# 01-Amplifier.net
KiCad netlist of a schematic drawn in Altium Designer
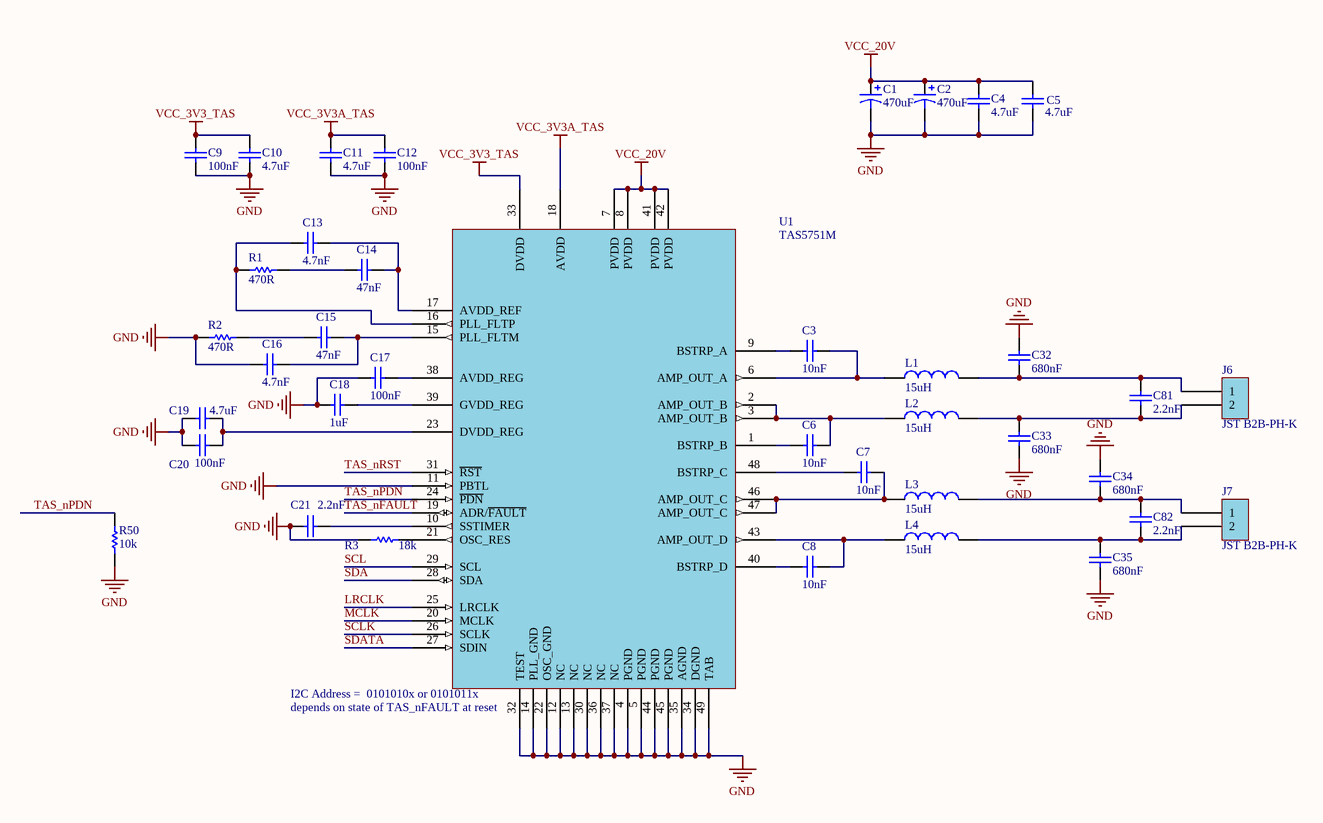
[diagram p0: 01-Amplifier.SchDoc]

(export (version "E")
  (design (tool "Eeschema 10.0.6"))
  (components
    (comp (ref "C1")
      (value "470uF")
      (footprint "Aptustech:Cap_POL_10mm_12.5mm_TH")
      (description "Aluminum Capacitor 470uF 25V TH 10mm 12.5mm")
      (fields (field (name "VOLTAGE") "25V") (field (name "TOLERANCE") "20%"))
      (libsource (lib "Cap_Aluminum") (part "470uF 25V 10mm 12.5mm"))
    )
    (comp (ref "C2")
      (value "470uF")
      (footprint "Aptustech:Cap_POL_10mm_12.5mm_TH")
      (description "Aluminum Capacitor 470uF 25V TH 10mm 12.5mm")
      (fields (field (name "VOLTAGE") "25V") (field (name "TOLERANCE") "20%"))
      (libsource (lib "Cap_Aluminum") (part "470uF 25V 10mm 12.5mm"))
    )
    (comp (ref "C3")
      (value "10nF")
      (footprint "Aptustech:CAPC3216X16N")
      (description "10nF 50V 1206 X7R")
      (fields (field (name "VOLTAGE") "50V") (field (name "TOLERANCE") "10%"))
      (libsource (lib "Cap_1206") (part "10nF 50V 1206 X7R"))
    )
    (comp (ref "C4")
      (value "4.7uF")
      (footprint "Aptustech:CAPC3216X16N")
      (description "4.7uF 50V 1206 X5R")
      (fields (field (name "VOLTAGE") "50V") (field (name "TOLERANCE") "10%"))
      (libsource (lib "Cap_1206") (part "4.7uF 50V 1206 X5R"))
    )
    (comp (ref "C5")
      (value "4.7uF")
      (footprint "Aptustech:CAPC3216X16N")
      (description "4.7uF 50V 1206 X5R")
      (fields (field (name "VOLTAGE") "50V") (field (name "TOLERANCE") "10%"))
      (libsource (lib "Cap_1206") (part "4.7uF 50V 1206 X5R"))
    )
    (comp (ref "C6")
      (value "10nF")
      (footprint "Aptustech:CAPC3216X16N")
      (description "10nF 50V 1206 X7R")
      (fields (field (name "VOLTAGE") "50V") (field (name "TOLERANCE") "10%"))
      (libsource (lib "Cap_1206") (part "10nF 50V 1206 X7R"))
    )
    (comp (ref "C7")
      (value "10nF")
      (footprint "Aptustech:CAPC3216X16N")
      (description "10nF 50V 1206 X7R")
      (fields (field (name "VOLTAGE") "50V") (field (name "TOLERANCE") "10%"))
      (libsource (lib "Cap_1206") (part "10nF 50V 1206 X7R"))
    )
    (comp (ref "C8")
      (value "10nF")
      (footprint "Aptustech:CAPC3216X16N")
      (description "10nF 50V 1206 X7R")
      (fields (field (name "VOLTAGE") "50V") (field (name "TOLERANCE") "10%"))
      (libsource (lib "Cap_1206") (part "10nF 50V 1206 X7R"))
    )
    (comp (ref "C9")
      (value "100nF")
      (footprint "Aptustech:CAPC1608X06N")
      (description "100nF 25V 0603 X5R")
      (fields (field (name "VOLTAGE") "25V") (field (name "TOLERANCE") "10%"))
      (libsource (lib "Cap_0603") (part "100nF 25V 0603 X5R"))
    )
    (comp (ref "C10")
      (value "4.7uF")
      (footprint "Aptustech:CAPC1608X06N")
      (description "4.7uF 10V 0603 X5R")
      (fields (field (name "VOLTAGE") "10V") (field (name "TOLERANCE") "10%"))
      (libsource (lib "Cap_0603") (part "4.7uF 10V 0603 X5R"))
    )
    (comp (ref "C11")
      (value "4.7uF")
      (footprint "Aptustech:CAPC1608X06N")
      (description "4.7uF 10V 0603 X5R")
      (fields (field (name "VOLTAGE") "10V") (field (name "TOLERANCE") "10%"))
      (libsource (lib "Cap_0603") (part "4.7uF 10V 0603 X5R"))
    )
    (comp (ref "C12")
      (value "100nF")
      (footprint "Aptustech:CAPC1608X06N")
      (description "100nF 25V 0603 X5R")
      (fields (field (name "VOLTAGE") "25V") (field (name "TOLERANCE") "10%"))
      (libsource (lib "Cap_0603") (part "100nF 25V 0603 X5R"))
    )
    (comp (ref "C13")
      (value "4.7nF")
      (footprint "Aptustech:CAPC1608X06N")
      (description "4.7nF 50V 0603 X7R")
      (fields (field (name "VOLTAGE") "50V") (field (name "TOLERANCE") "10%"))
      (libsource (lib "Cap_0603") (part "4.7nF 50V 0603 X7R"))
    )
    (comp (ref "C14")
      (value "47nF")
      (footprint "Aptustech:CAPC1608X06N")
      (description "47nF 50V 0603 X7R")
      (fields (field (name "VOLTAGE") "50V") (field (name "TOLERANCE") "10%"))
      (libsource (lib "Cap_0603") (part "47nF 50V 0603 X7R"))
    )
    (comp (ref "C15")
      (value "47nF")
      (footprint "Aptustech:CAPC1608X06N")
      (description "47nF 50V 0603 X7R")
      (fields (field (name "VOLTAGE") "50V") (field (name "TOLERANCE") "10%"))
      (libsource (lib "Cap_0603") (part "47nF 50V 0603 X7R"))
    )
    (comp (ref "C16")
      (value "4.7nF")
      (footprint "Aptustech:CAPC1608X06N")
      (description "4.7nF 50V 0603 X7R")
      (fields (field (name "VOLTAGE") "50V") (field (name "TOLERANCE") "10%"))
      (libsource (lib "Cap_0603") (part "4.7nF 50V 0603 X7R"))
    )
    (comp (ref "C17")
      (value "100nF")
      (footprint "Aptustech:CAPC1608X06N")
      (description "100nF 25V 0603 X5R")
      (fields (field (name "VOLTAGE") "25V") (field (name "TOLERANCE") "10%"))
      (libsource (lib "Cap_0603") (part "100nF 25V 0603 X5R"))
    )
    (comp (ref "C18")
      (value "1uF")
      (footprint "Aptustech:CAPC1608X06N")
      (description "1uF 16V 0603 X7R")
      (fields (field (name "VOLTAGE") "16V") (field (name "TOLERANCE") "10%"))
      (libsource (lib "Cap_0603") (part "1uF 16V 0603 X7R"))
    )
    (comp (ref "C19")
      (value "4.7uF")
      (footprint "Aptustech:CAPC1608X06N")
      (description "4.7uF 10V 0603 X5R")
      (fields (field (name "VOLTAGE") "10V") (field (name "TOLERANCE") "10%"))
      (libsource (lib "Cap_0603") (part "4.7uF 10V 0603 X5R"))
    )
    (comp (ref "C20")
      (value "100nF")
      (footprint "Aptustech:CAPC1608X06N")
      (description "100nF 25V 0603 X5R")
      (fields (field (name "VOLTAGE") "25V") (field (name "TOLERANCE") "10%"))
      (libsource (lib "Cap_0603") (part "100nF 25V 0603 X5R"))
    )
    (comp (ref "C21")
      (value "2.2nF")
      (footprint "Aptustech:CAPC1608X06N")
      (description "2.2nF 50V 0603 X7R")
      (fields (field (name "VOLTAGE") "50V") (field (name "TOLERANCE") "10%"))
      (libsource (lib "Cap_0603") (part "2.2nF 50V 0603 X7R"))
    )
    (comp (ref "C32")
      (value "680nF")
      (footprint "Aptustech:CAPC3216X16N")
      (description "680nF 50V 1206 C0G")
      (fields (field (name "VOLTAGE") "50V") (field (name "TOLERANCE") "10%"))
      (libsource (lib "Cap_1206") (part "680nF 50V 1206 C0G"))
    )
    (comp (ref "C33")
      (value "680nF")
      (footprint "Aptustech:CAPC3216X16N")
      (description "680nF 50V 1206 C0G")
      (fields (field (name "VOLTAGE") "50V") (field (name "TOLERANCE") "10%"))
      (libsource (lib "Cap_1206") (part "680nF 50V 1206 C0G"))
    )
    (comp (ref "C34")
      (value "680nF")
      (footprint "Aptustech:CAPC3216X16N")
      (description "680nF 50V 1206 C0G")
      (fields (field (name "VOLTAGE") "50V") (field (name "TOLERANCE") "10%"))
      (libsource (lib "Cap_1206") (part "680nF 50V 1206 C0G"))
    )
    (comp (ref "C35")
      (value "680nF")
      (footprint "Aptustech:CAPC3216X16N")
      (description "680nF 50V 1206 C0G")
      (fields (field (name "VOLTAGE") "50V") (field (name "TOLERANCE") "10%"))
      (libsource (lib "Cap_1206") (part "680nF 50V 1206 C0G"))
    )
    (comp (ref "C81")
      (value "2.2nF")
      (footprint "Aptustech:CAPC1608X06N")
      (description "2.2nF 50V 0603 X7R")
      (fields (field (name "VOLTAGE") "50V") (field (name "TOLERANCE") "10%"))
      (libsource (lib "Cap_0603") (part "2.2nF 50V 0603 X7R"))
    )
    (comp (ref "C82")
      (value "2.2nF")
      (footprint "Aptustech:CAPC1608X06N")
      (description "2.2nF 50V 0603 X7R")
      (fields (field (name "VOLTAGE") "50V") (field (name "TOLERANCE") "10%"))
      (libsource (lib "Cap_0603") (part "2.2nF 50V 0603 X7R"))
    )
    (comp (ref "J6")
      (value "JST B2B-PH-K")
      (footprint "Aptustech:JST B2B-PH-K")
      (fields (field (name "PARTNUMBER") "B2B-PH-K") (field (name "MANUFACTURER") "JST"))
      (libsource (lib "Connectors") (part "JST B2B-PH-K"))
    )
    (comp (ref "J7")
      (value "JST B2B-PH-K")
      (footprint "Aptustech:JST B2B-PH-K")
      (fields (field (name "PARTNUMBER") "B2B-PH-K") (field (name "MANUFACTURER") "JST"))
      (libsource (lib "Connectors") (part "JST B2B-PH-K"))
    )
    (comp (ref "L1")
      (value "15uH")
      (footprint "Aptustech:1255AY")
      (description "1255AY-150M")
      (fields (field (name "MANUFACTURER") "Murata"))
      (libsource (lib "Inductor") (part "1255AY-150M"))
    )
    (comp (ref "L2")
      (value "15uH")
      (footprint "Aptustech:1255AY")
      (description "1255AY-150M")
      (fields (field (name "MANUFACTURER") "Murata"))
      (libsource (lib "Inductor") (part "1255AY-150M"))
    )
    (comp (ref "L3")
      (value "15uH")
      (footprint "Aptustech:1255AY")
      (description "1255AY-150M")
      (fields (field (name "MANUFACTURER") "Murata"))
      (libsource (lib "Inductor") (part "1255AY-150M"))
    )
    (comp (ref "L4")
      (value "15uH")
      (footprint "Aptustech:1255AY")
      (description "1255AY-150M")
      (fields (field (name "MANUFACTURER") "Murata"))
      (libsource (lib "Inductor") (part "1255AY-150M"))
    )
    (comp (ref "R1")
      (value "470R")
      (footprint "Aptustech:RESC1608X06N")
      (description "Resistor 470R 0603 1%")
      (fields (field (name "TOLERANCE") "1%") (field (name "Comment") "470R_0603"))
      (libsource (lib "Res_0603") (part "470R"))
    )
    (comp (ref "R2")
      (value "470R")
      (footprint "Aptustech:RESC1608X06N")
      (description "Resistor 470R 0603 1%")
      (fields (field (name "TOLERANCE") "1%") (field (name "Comment") "470R_0603"))
      (libsource (lib "Res_0603") (part "470R"))
    )
    (comp (ref "R3")
      (value "18k")
      (footprint "Aptustech:RESC1608X06N")
      (description "Resistor 18k 0603 1%")
      (fields (field (name "TOLERANCE") "1%") (field (name "Comment") "18k_0603"))
      (libsource (lib "Res_0603") (part "18k"))
    )
    (comp (ref "R50")
      (value "10k")
      (footprint "Aptustech:RESC1608X06N")
      (description "Resistor 10k 0603 1%")
      (fields (field (name "TOLERANCE") "1%") (field (name "Comment") "10k_0603"))
      (libsource (lib "Res_0603") (part "10k"))
    )
    (comp (ref "U1")
      (value "TAS5751M")
      (footprint "Aptustech:TSSOP50P810X120_HS-49M")
      (description "TAS5751M - Digital Input Audio Power Amplifier with EQ and 3-Band AGL")
      (fields (field (name "MANUFACTURER") "TI"))
      (libsource (lib "Audio") (part "TAS5751M"))
    )
  )
  (nets
    (net (code "1") (name "/LRCLK") (class "Default")
      (node (ref "U1") (pin "25") (pinfunction "LRCLK_25") (pintype "input"))
    )
    (net (code "2") (name "/MCLK") (class "Default")
      (node (ref "U1") (pin "20") (pinfunction "MCLK_20") (pintype "input"))
    )
    (net (code "3") (name "/SCL") (class "Default")
      (node (ref "U1") (pin "29") (pinfunction "SCL_29") (pintype "input"))
    )
    (net (code "4") (name "/SCLK") (class "Default")
      (node (ref "U1") (pin "26") (pinfunction "SCLK_26") (pintype "input"))
    )
    (net (code "5") (name "/SDA") (class "Default")
      (node (ref "U1") (pin "28") (pinfunction "SDA_28") (pintype "bidirectional"))
    )
    (net (code "6") (name "/SDATA") (class "Default")
      (node (ref "U1") (pin "27") (pinfunction "SDIN_27") (pintype "input"))
    )
    (net (code "7") (name "/TAS_nFAULT") (class "Default")
      (node (ref "U1") (pin "19") (pinfunction "ADR/~{FAULT}_19") (pintype "bidirectional"))
    )
    (net (code "8") (name "/TAS_nPDN") (class "Default")
      (node (ref "R50") (pin "1") (pinfunction "1_1") (pintype "passive"))
      (node (ref "U1") (pin "24") (pinfunction "~{PDN}_24") (pintype "input"))
    )
    (net (code "9") (name "/TAS_nRST") (class "Default")
      (node (ref "U1") (pin "31") (pinfunction "~{RST}_31") (pintype "input"))
    )
    (net (code "10") (name "GND") (class "Default")
      (node (ref "C1") (pin "2") (pinfunction "2_2") (pintype "passive"))
      (node (ref "C10") (pin "1") (pinfunction "1_1") (pintype "passive"))
      (node (ref "C11") (pin "1") (pinfunction "1_1") (pintype "passive"))
      (node (ref "C12") (pin "1") (pinfunction "1_1") (pintype "passive"))
      (node (ref "C16") (pin "1") (pinfunction "1_1") (pintype "passive"))
      (node (ref "C17") (pin "2") (pinfunction "2_2") (pintype "passive"))
      (node (ref "C18") (pin "1") (pinfunction "1_1") (pintype "passive"))
      (node (ref "C19") (pin "2") (pinfunction "2_2") (pintype "passive"))
      (node (ref "C2") (pin "2") (pinfunction "2_2") (pintype "passive"))
      (node (ref "C20") (pin "2") (pinfunction "2_2") (pintype "passive"))
      (node (ref "C21") (pin "1") (pinfunction "1_1") (pintype "passive"))
      (node (ref "C32") (pin "1") (pinfunction "1_1") (pintype "passive"))
      (node (ref "C33") (pin "1") (pinfunction "1_1") (pintype "passive"))
      (node (ref "C34") (pin "1") (pinfunction "1_1") (pintype "passive"))
      (node (ref "C35") (pin "1") (pinfunction "1_1") (pintype "passive"))
      (node (ref "C4") (pin "1") (pinfunction "1_1") (pintype "passive"))
      (node (ref "C5") (pin "1") (pinfunction "1_1") (pintype "passive"))
      (node (ref "C9") (pin "1") (pinfunction "1_1") (pintype "passive"))
      (node (ref "R2") (pin "1") (pinfunction "1_1") (pintype "passive"))
      (node (ref "R3") (pin "1") (pinfunction "1_1") (pintype "passive"))
      (node (ref "R50") (pin "2") (pinfunction "2_2") (pintype "passive"))
      (node (ref "U1") (pin "11") (pinfunction "PBTL_11") (pintype "input"))
      (node (ref "U1") (pin "12") (pinfunction "NC_12") (pintype "passive"))
      (node (ref "U1") (pin "13") (pinfunction "NC_13") (pintype "passive"))
      (node (ref "U1") (pin "14") (pinfunction "PLL_GND_14") (pintype "power_in"))
      (node (ref "U1") (pin "22") (pinfunction "OSC_GND_22") (pintype "power_in"))
      (node (ref "U1") (pin "30") (pinfunction "NC_30") (pintype "passive"))
      (node (ref "U1") (pin "32") (pinfunction "TEST_32") (pintype "passive"))
      (node (ref "U1") (pin "34") (pinfunction "DGND_34") (pintype "power_in"))
      (node (ref "U1") (pin "35") (pinfunction "AGND_35") (pintype "power_in"))
      (node (ref "U1") (pin "36") (pinfunction "NC_36") (pintype "passive"))
      (node (ref "U1") (pin "37") (pinfunction "NC_37") (pintype "passive"))
      (node (ref "U1") (pin "4") (pinfunction "PGND_4") (pintype "power_in"))
      (node (ref "U1") (pin "44") (pinfunction "PGND_44") (pintype "power_in"))
      (node (ref "U1") (pin "45") (pinfunction "PGND_45") (pintype "power_in"))
      (node (ref "U1") (pin "49") (pinfunction "TAB_49") (pintype "power_in"))
      (node (ref "U1") (pin "5") (pinfunction "PGND_5") (pintype "power_in"))
    )
    (net (code "11") (name "Net-(C6-Pad2)") (class "Default")
      (node (ref "C6") (pin "2") (pinfunction "2_2") (pintype "passive"))
      (node (ref "L2") (pin "1") (pinfunction "1_1") (pintype "passive"))
      (node (ref "U1") (pin "2") (pinfunction "AMP_OUT_B_2") (pintype "output"))
      (node (ref "U1") (pin "3") (pinfunction "AMP_OUT_B_3") (pintype "output"))
    )
    (net (code "12") (name "Net-(C7-Pad2)") (class "Default")
      (node (ref "C7") (pin "2") (pinfunction "2_2") (pintype "passive"))
      (node (ref "L3") (pin "1") (pinfunction "1_1") (pintype "passive"))
      (node (ref "U1") (pin "46") (pinfunction "AMP_OUT_C_46") (pintype "output"))
      (node (ref "U1") (pin "47") (pinfunction "AMP_OUT_C_47") (pintype "output"))
    )
    (net (code "13") (name "Net-(C14-Pad1)") (class "Default")
      (node (ref "C14") (pin "1") (pinfunction "1_1") (pintype "passive"))
      (node (ref "R1") (pin "2") (pinfunction "2_2") (pintype "passive"))
    )
    (net (code "14") (name "Net-(C15-Pad1)") (class "Default")
      (node (ref "C15") (pin "1") (pinfunction "1_1") (pintype "passive"))
      (node (ref "R2") (pin "2") (pinfunction "2_2") (pintype "passive"))
    )
    (net (code "15") (name "Net-(C32-Pad2)") (class "Default")
      (node (ref "C32") (pin "2") (pinfunction "2_2") (pintype "passive"))
      (node (ref "C81") (pin "2") (pinfunction "2_2") (pintype "passive"))
      (node (ref "J6") (pin "1") (pinfunction "1_1") (pintype "passive"))
      (node (ref "L1") (pin "2") (pinfunction "2_2") (pintype "passive"))
    )
    (net (code "16") (name "Net-(C33-Pad2)") (class "Default")
      (node (ref "C33") (pin "2") (pinfunction "2_2") (pintype "passive"))
      (node (ref "C81") (pin "1") (pinfunction "1_1") (pintype "passive"))
      (node (ref "J6") (pin "2") (pinfunction "2_2") (pintype "passive"))
      (node (ref "L2") (pin "2") (pinfunction "2_2") (pintype "passive"))
    )
    (net (code "17") (name "Net-(C34-Pad2)") (class "Default")
      (node (ref "C34") (pin "2") (pinfunction "2_2") (pintype "passive"))
      (node (ref "C82") (pin "2") (pinfunction "2_2") (pintype "passive"))
      (node (ref "J7") (pin "1") (pinfunction "1_1") (pintype "passive"))
      (node (ref "L3") (pin "2") (pinfunction "2_2") (pintype "passive"))
    )
    (net (code "18") (name "Net-(C35-Pad2)") (class "Default")
      (node (ref "C35") (pin "2") (pinfunction "2_2") (pintype "passive"))
      (node (ref "C82") (pin "1") (pinfunction "1_1") (pintype "passive"))
      (node (ref "J7") (pin "2") (pinfunction "2_2") (pintype "passive"))
      (node (ref "L4") (pin "2") (pinfunction "2_2") (pintype "passive"))
    )
    (net (code "19") (name "Net-(U1-AMP_OUT_A)") (class "Default")
      (node (ref "C3") (pin "2") (pinfunction "2_2") (pintype "passive"))
      (node (ref "L1") (pin "1") (pinfunction "1_1") (pintype "passive"))
      (node (ref "U1") (pin "6") (pinfunction "AMP_OUT_A_6") (pintype "output"))
    )
    (net (code "20") (name "Net-(U1-AMP_OUT_D)") (class "Default")
      (node (ref "C8") (pin "2") (pinfunction "2_2") (pintype "passive"))
      (node (ref "L4") (pin "1") (pinfunction "1_1") (pintype "passive"))
      (node (ref "U1") (pin "43") (pinfunction "AMP_OUT_D_43") (pintype "output"))
    )
    (net (code "21") (name "Net-(U1-AVDD_REF)") (class "Default")
      (node (ref "C13") (pin "2") (pinfunction "2_2") (pintype "passive"))
      (node (ref "C14") (pin "2") (pinfunction "2_2") (pintype "passive"))
      (node (ref "U1") (pin "17") (pinfunction "AVDD_REF_17") (pintype "power_in"))
    )
    (net (code "22") (name "Net-(U1-AVDD_REG)") (class "Default")
      (node (ref "C17") (pin "1") (pinfunction "1_1") (pintype "passive"))
      (node (ref "U1") (pin "38") (pinfunction "AVDD_REG_38") (pintype "power_in"))
    )
    (net (code "23") (name "Net-(U1-BSTRP_A)") (class "Default")
      (node (ref "C3") (pin "1") (pinfunction "1_1") (pintype "passive"))
      (node (ref "U1") (pin "9") (pinfunction "BSTRP_A_9") (pintype "power_in"))
    )
    (net (code "24") (name "Net-(U1-BSTRP_B)") (class "Default")
      (node (ref "C6") (pin "1") (pinfunction "1_1") (pintype "passive"))
      (node (ref "U1") (pin "1") (pinfunction "BSTRP_B_1") (pintype "power_in"))
    )
    (net (code "25") (name "Net-(U1-BSTRP_C)") (class "Default")
      (node (ref "C7") (pin "1") (pinfunction "1_1") (pintype "passive"))
      (node (ref "U1") (pin "48") (pinfunction "BSTRP_C_48") (pintype "power_in"))
    )
    (net (code "26") (name "Net-(U1-BSTRP_D)") (class "Default")
      (node (ref "C8") (pin "1") (pinfunction "1_1") (pintype "passive"))
      (node (ref "U1") (pin "40") (pinfunction "BSTRP_D_40") (pintype "power_in"))
    )
    (net (code "27") (name "Net-(U1-DVDD_REG)") (class "Default")
      (node (ref "C19") (pin "1") (pinfunction "1_1") (pintype "passive"))
      (node (ref "C20") (pin "1") (pinfunction "1_1") (pintype "passive"))
      (node (ref "U1") (pin "23") (pinfunction "DVDD_REG_23") (pintype "power_in"))
    )
    (net (code "28") (name "Net-(U1-GVDD_REG)") (class "Default")
      (node (ref "C18") (pin "2") (pinfunction "2_2") (pintype "passive"))
      (node (ref "U1") (pin "39") (pinfunction "GVDD_REG_39") (pintype "power_in"))
    )
    (net (code "29") (name "Net-(U1-OSC_RES)") (class "Default")
      (node (ref "R3") (pin "2") (pinfunction "2_2") (pintype "passive"))
      (node (ref "U1") (pin "21") (pinfunction "OSC_RES_21") (pintype "output"))
    )
    (net (code "30") (name "Net-(U1-PLL_FLTM)") (class "Default")
      (node (ref "C15") (pin "2") (pinfunction "2_2") (pintype "passive"))
      (node (ref "C16") (pin "2") (pinfunction "2_2") (pintype "passive"))
      (node (ref "U1") (pin "15") (pinfunction "PLL_FLTM_15") (pintype "output"))
    )
    (net (code "31") (name "Net-(U1-PLL_FLTP)") (class "Default")
      (node (ref "C13") (pin "1") (pinfunction "1_1") (pintype "passive"))
      (node (ref "R1") (pin "1") (pinfunction "1_1") (pintype "passive"))
      (node (ref "U1") (pin "16") (pinfunction "PLL_FLTP_16") (pintype "output"))
    )
    (net (code "32") (name "Net-(U1-SSTIMER)") (class "Default")
      (node (ref "C21") (pin "2") (pinfunction "2_2") (pintype "passive"))
      (node (ref "U1") (pin "10") (pinfunction "SSTIMER_10") (pintype "output"))
    )
    (net (code "33") (name "VCC_3V3A_TAS") (class "Default")
      (node (ref "C11") (pin "2") (pinfunction "2_2") (pintype "passive"))
      (node (ref "C12") (pin "2") (pinfunction "2_2") (pintype "passive"))
      (node (ref "U1") (pin "18") (pinfunction "AVDD_18") (pintype "power_in"))
    )
    (net (code "34") (name "VCC_3V3_TAS") (class "Default")
      (node (ref "C10") (pin "2") (pinfunction "2_2") (pintype "passive"))
      (node (ref "C9") (pin "2") (pinfunction "2_2") (pintype "passive"))
      (node (ref "U1") (pin "33") (pinfunction "DVDD_33") (pintype "power_in"))
    )
    (net (code "35") (name "VCC_20V") (class "Default")
      (node (ref "C1") (pin "1") (pinfunction "1_1") (pintype "passive"))
      (node (ref "C2") (pin "1") (pinfunction "1_1") (pintype "passive"))
      (node (ref "C4") (pin "2") (pinfunction "2_2") (pintype "passive"))
      (node (ref "C5") (pin "2") (pinfunction "2_2") (pintype "passive"))
      (node (ref "U1") (pin "41") (pinfunction "PVDD_41") (pintype "power_in"))
      (node (ref "U1") (pin "42") (pinfunction "PVDD_42") (pintype "power_in"))
      (node (ref "U1") (pin "7") (pinfunction "PVDD_7") (pintype "power_in"))
      (node (ref "U1") (pin "8") (pinfunction "PVDD_8") (pintype "power_in"))
    )
  )
)
